# Sheet4.net
KiCad netlist of a schematic drawn in Altium Designer
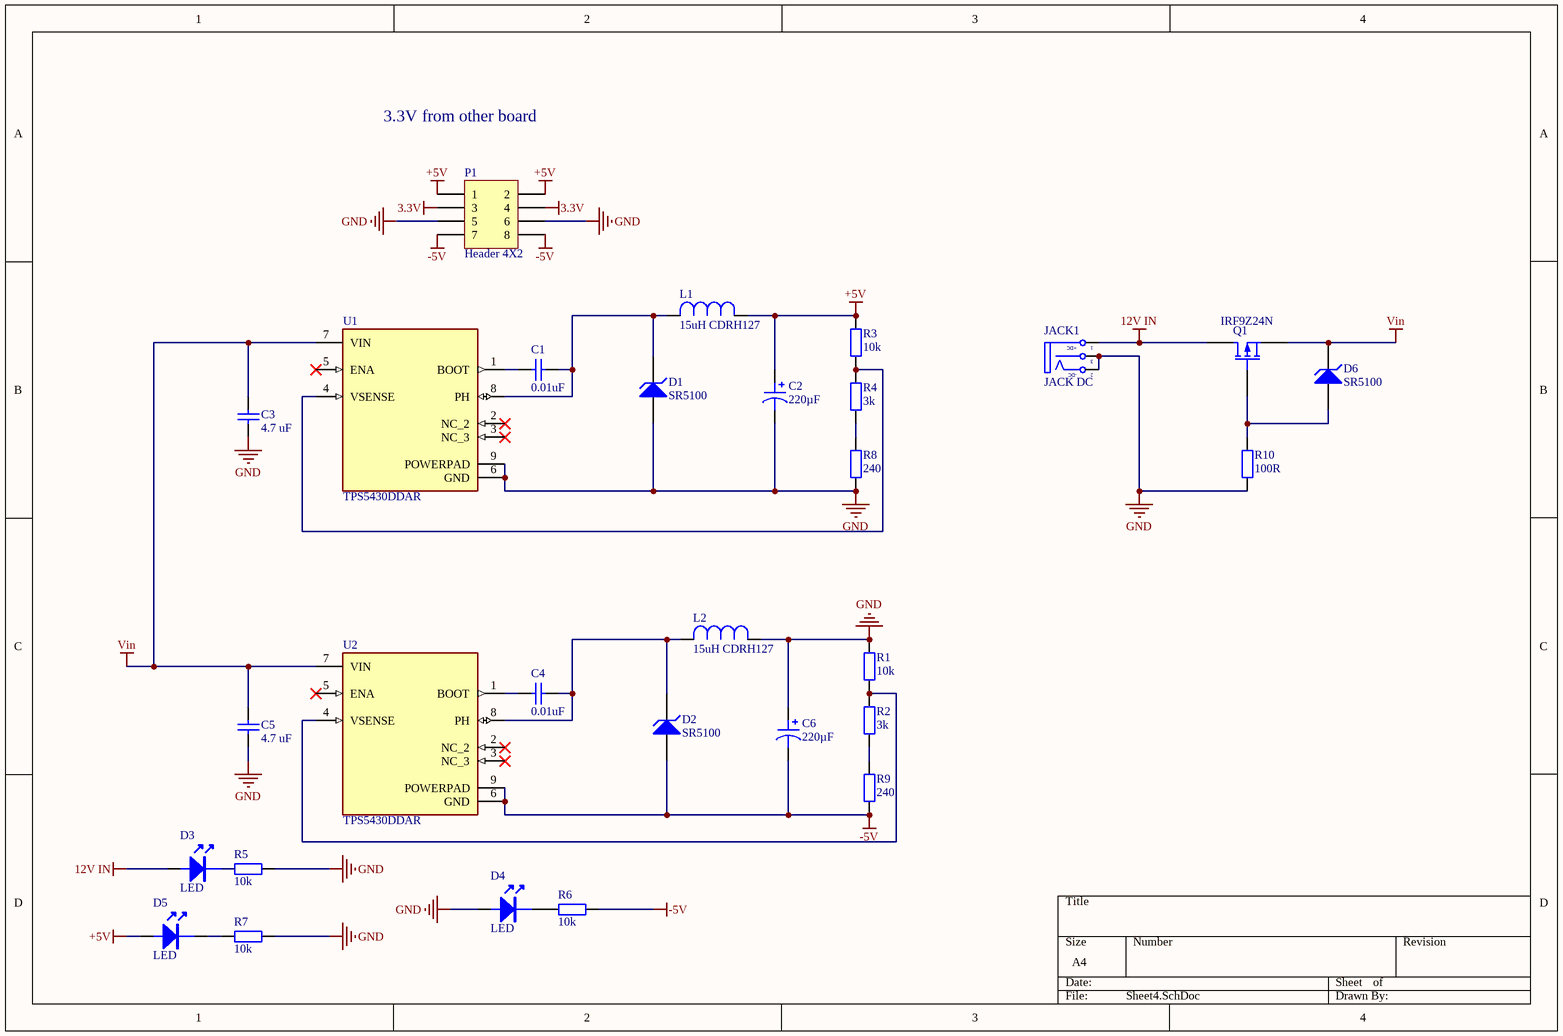
[diagram p0: Sheet4.SchDoc]

(export (version "E")
  (design (tool "Eeschema 10.0.6"))
  (components
    (comp (ref "C1")
      (value "0.01uF")
      (footprint "0805 CAP")
      (fields (field (name "PUBLISHER") "Altium Limited"))
      (libsource (lib "ThinhNguyenLib") (part "CAP CERAMIC"))
    )
    (comp (ref "C2")
      (value "220µF")
      (footprint "CAP POL 2917_7343")
      (description "CAP TANT 330UF 20% 10V 2917")
      (fields (field (name "PART NUMBER") "TPSE337M010R0040") (field (name "MANUFACTURER") "AVX Corporation"))
      (libsource (lib "Celestial Altium Library - altium_library") (part "Polarised Capacitor"))
    )
    (comp (ref "C3")
      (value "4.7 uF")
      (footprint "0805 CAP")
      (fields (field (name "PUBLISHER") "Altium Limited"))
      (libsource (lib "ThinhNguyenLib") (part "CAP CERAMIC"))
    )
    (comp (ref "C4")
      (value "0.01uF")
      (footprint "0805 CAP")
      (fields (field (name "PUBLISHER") "Altium Limited"))
      (libsource (lib "ThinhNguyenLib") (part "CAP CERAMIC"))
    )
    (comp (ref "C5")
      (value "4.7 uF")
      (footprint "0805 CAP")
      (fields (field (name "PUBLISHER") "Altium Limited"))
      (libsource (lib "ThinhNguyenLib") (part "CAP CERAMIC"))
    )
    (comp (ref "C6")
      (value "220µF")
      (footprint "CAP POL 2917_7343")
      (description "CAP TANT 330UF 20% 10V 2917")
      (fields (field (name "PART NUMBER") "TPSE337M010R0040") (field (name "MANUFACTURER") "AVX Corporation"))
      (libsource (lib "Celestial Altium Library - altium_library") (part "Polarised Capacitor"))
    )
    (comp (ref "D1")
      (value "SR5100")
      (footprint "DIODE-0.4")
      (description "Zener Diode")
      (fields (field (name "PUBLISHER") "Altium Limited"))
      (libsource (lib "Miscellaneous Devices") (part "D Zener"))
    )
    (comp (ref "D2")
      (value "SR5100")
      (footprint "DIODE-0.4")
      (description "Zener Diode")
      (fields (field (name "PUBLISHER") "Altium Limited"))
      (libsource (lib "Miscellaneous Devices") (part "D Zener"))
    )
    (comp (ref "D3") (value "LED") (footprint "LED SMD 0805") (libsource (lib "ThinhNguyenLib") (part "LED")))
    (comp (ref "D4") (value "LED") (footprint "LED SMD 0805") (libsource (lib "ThinhNguyenLib") (part "LED")))
    (comp (ref "D5") (value "LED") (footprint "LED SMD 0805") (libsource (lib "ThinhNguyenLib") (part "LED")))
    (comp (ref "D6")
      (value "SR5100")
      (footprint "DIODE-0.4")
      (description "Zener Diode")
      (fields (field (name "PUBLISHER") "Altium Limited"))
      (libsource (lib "Miscellaneous Devices") (part "D Zener"))
    )
    (comp (ref "JACK1")
      (value "JACK DC")
      (footprint "JACK DC")
      (libsource (lib "ThinhNguyenLib") (part "JACK DC"))
    )
    (comp (ref "L1")
      (value "15uH CDRH127")
      (footprint "IND_CDRH127/LDNP-470MC_SUM")
      (description "47ÂµH Shielded Inductor 3.25A 78mOhm Max Nonstandard")
      (fields (field (name "DIGI-KEY_PART_NUMBER") "308-1339-1-ND") (field (name "MF") "Sumida America"))
      (libsource (lib "CDRH127_LDNP-470MC") (part "CDRH127/LDNP-470MC"))
    )
    (comp (ref "L2")
      (value "15uH CDRH127")
      (footprint "IND_CDRH127/LDNP-470MC_SUM")
      (description "47ÂµH Shielded Inductor 3.25A 78mOhm Max Nonstandard")
      (fields (field (name "DIGI-KEY_PART_NUMBER") "308-1339-1-ND") (field (name "MF") "Sumida America"))
      (libsource (lib "CDRH127_LDNP-470MC") (part "CDRH127/LDNP-470MC"))
    )
    (comp (ref "P1")
      (value "Header 4X2")
      (footprint "HDR2X4")
      (fields (field (name "PUBLISHER") "Altium Limited"))
      (libsource (lib "ThinhNguyenLib") (part "Header 4X2"))
    )
    (comp (ref "Q1")
      (value "IRF9Z24N")
      (footprint "TO-220AB")
      (description "P-Channel MOSFET")
      (fields (field (name "PUBLISHER") "Altium Limited"))
      (libsource (lib "Miscellaneous Devices") (part "MOSFET-P"))
    )
    (comp (ref "R1")
      (value "10k")
      (footprint "0805 RESISTOR")
      (libsource (lib "ThinhNguyenLib") (part "RESISTOR"))
    )
    (comp (ref "R2")
      (value "3k")
      (footprint "0805 RESISTOR")
      (libsource (lib "ThinhNguyenLib") (part "RESISTOR"))
    )
    (comp (ref "R3")
      (value "10k")
      (footprint "0805 RESISTOR")
      (libsource (lib "ThinhNguyenLib") (part "RESISTOR"))
    )
    (comp (ref "R4")
      (value "3k")
      (footprint "0805 RESISTOR")
      (libsource (lib "ThinhNguyenLib") (part "RESISTOR"))
    )
    (comp (ref "R5")
      (value "10k")
      (footprint "0805 RESISTOR")
      (libsource (lib "ThinhNguyenLib") (part "RESISTOR"))
    )
    (comp (ref "R6")
      (value "10k")
      (footprint "0805 RESISTOR")
      (libsource (lib "ThinhNguyenLib") (part "RESISTOR"))
    )
    (comp (ref "R7")
      (value "10k")
      (footprint "0805 RESISTOR")
      (libsource (lib "ThinhNguyenLib") (part "RESISTOR"))
    )
    (comp (ref "R8")
      (value "240")
      (footprint "0805 RESISTOR")
      (libsource (lib "ThinhNguyenLib") (part "RESISTOR"))
    )
    (comp (ref "R9")
      (value "240")
      (footprint "0805 RESISTOR")
      (libsource (lib "ThinhNguyenLib") (part "RESISTOR"))
    )
    (comp (ref "R10")
      (value "100R")
      (footprint "0805 RESISTOR")
      (libsource (lib "ThinhNguyenLib") (part "RESISTOR"))
    )
    (comp (ref "U1")
      (value "TPS5430DDAR")
      (footprint "CONV_TPS5430DDAR:CONV_TPS5430DDAR")
      (description "5.5V to 36V Input, 3A, 500kHz Step-Down Converter 8-SO PowerPAD -40 to 125")
      (fields (field (name "DIGI-KEY_PART_NUMBER") "296-26988-1-ND") (field (name "MF") "Texas Instruments"))
      (libsource (lib "TPS5430DDAR") (part "TPS5430DDAR"))
    )
    (comp (ref "U2")
      (value "TPS5430DDAR")
      (footprint "CONV_TPS5430DDAR:CONV_TPS5430DDAR")
      (description "5.5V to 36V Input, 3A, 500kHz Step-Down Converter 8-SO PowerPAD -40 to 125")
      (fields (field (name "DIGI-KEY_PART_NUMBER") "296-26988-1-ND") (field (name "MF") "Texas Instruments"))
      (libsource (lib "TPS5430DDAR") (part "TPS5430DDAR"))
    )
  )
  (nets
    (net (code "1") (name "+5V") (class "Default")
      (node (ref "C2") (pin "1") (pinfunction "1_1") (pintype "passive"))
      (node (ref "D5") (pin "1") (pinfunction "1_1") (pintype "passive"))
      (node (ref "L1") (pin "1") (pinfunction "1_1") (pintype "passive"))
      (node (ref "P1") (pin "1") (pinfunction "1_1") (pintype "passive"))
      (node (ref "P1") (pin "2") (pinfunction "2_2") (pintype "passive"))
      (node (ref "R3") (pin "2") (pinfunction "2_2") (pintype "passive"))
    )
    (net (code "2") (name "-5V") (class "Default")
      (node (ref "C6") (pin "2") (pinfunction "2_2") (pintype "passive"))
      (node (ref "D2") (pin "1") (pinfunction "A_1") (pintype "passive"))
      (node (ref "P1") (pin "7") (pinfunction "7_7") (pintype "passive"))
      (node (ref "P1") (pin "8") (pinfunction "8_8") (pintype "passive"))
      (node (ref "R6") (pin "2") (pinfunction "2_2") (pintype "passive"))
      (node (ref "R9") (pin "1") (pinfunction "1_1") (pintype "passive"))
      (node (ref "U2") (pin "6") (pinfunction "GND_6") (pintype "power_in"))
      (node (ref "U2") (pin "9") (pinfunction "POWERPAD_9") (pintype "power_in"))
    )
    (net (code "3") (name "3.3V") (class "Default")
      (node (ref "P1") (pin "3") (pinfunction "3_3") (pintype "passive"))
      (node (ref "P1") (pin "4") (pinfunction "4_4") (pintype "passive"))
    )
    (net (code "4") (name "12V IN") (class "Default")
      (node (ref "D3") (pin "1") (pinfunction "1_1") (pintype "passive"))
      (node (ref "JACK1") (pin "1") (pinfunction "T_1") (pintype "passive"))
      (node (ref "Q1") (pin "1") (pinfunction "D_1") (pintype "passive"))
    )
    (net (code "5") (name "GND") (class "Default")
      (node (ref "C2") (pin "2") (pinfunction "2_2") (pintype "passive"))
      (node (ref "C3") (pin "1") (pinfunction "1_1") (pintype "passive"))
      (node (ref "C5") (pin "1") (pinfunction "1_1") (pintype "passive"))
      (node (ref "C6") (pin "1") (pinfunction "1_1") (pintype "passive"))
      (node (ref "D1") (pin "1") (pinfunction "A_1") (pintype "passive"))
      (node (ref "D4") (pin "1") (pinfunction "1_1") (pintype "passive"))
      (node (ref "JACK1") (pin "2") (pinfunction "TN_2") (pintype "passive"))
      (node (ref "JACK1") (pin "3") (pinfunction "S_3") (pintype "power_in"))
      (node (ref "L2") (pin "1") (pinfunction "1_1") (pintype "passive"))
      (node (ref "P1") (pin "5") (pinfunction "5_5") (pintype "passive"))
      (node (ref "P1") (pin "6") (pinfunction "6_6") (pintype "passive"))
      (node (ref "R1") (pin "2") (pinfunction "2_2") (pintype "passive"))
      (node (ref "R10") (pin "1") (pinfunction "1_1") (pintype "passive"))
      (node (ref "R5") (pin "2") (pinfunction "2_2") (pintype "passive"))
      (node (ref "R7") (pin "2") (pinfunction "2_2") (pintype "passive"))
      (node (ref "R8") (pin "1") (pinfunction "1_1") (pintype "passive"))
      (node (ref "U1") (pin "6") (pinfunction "GND_6") (pintype "power_in"))
      (node (ref "U1") (pin "9") (pinfunction "POWERPAD_9") (pintype "power_in"))
    )
    (net (code "6") (name "Net-(D1-K)") (class "Default")
      (node (ref "C1") (pin "2") (pinfunction "2_2") (pintype "passive"))
      (node (ref "D1") (pin "2") (pinfunction "K_2") (pintype "passive"))
      (node (ref "L1") (pin "2") (pinfunction "2_2") (pintype "passive"))
      (node (ref "U1") (pin "8") (pinfunction "PH_8") (pintype "bidirectional"))
    )
    (net (code "7") (name "Net-(D2-K)") (class "Default")
      (node (ref "C4") (pin "2") (pinfunction "2_2") (pintype "passive"))
      (node (ref "D2") (pin "2") (pinfunction "K_2") (pintype "passive"))
      (node (ref "L2") (pin "2") (pinfunction "2_2") (pintype "passive"))
      (node (ref "U2") (pin "8") (pinfunction "PH_8") (pintype "bidirectional"))
    )
    (net (code "8") (name "Net-(D3-Pad2)") (class "Default")
      (node (ref "D3") (pin "2") (pinfunction "2_2") (pintype "passive"))
      (node (ref "R5") (pin "1") (pinfunction "1_1") (pintype "passive"))
    )
    (net (code "9") (name "Net-(D4-Pad2)") (class "Default")
      (node (ref "D4") (pin "2") (pinfunction "2_2") (pintype "passive"))
      (node (ref "R6") (pin "1") (pinfunction "1_1") (pintype "passive"))
    )
    (net (code "10") (name "Net-(D5-Pad2)") (class "Default")
      (node (ref "D5") (pin "2") (pinfunction "2_2") (pintype "passive"))
      (node (ref "R7") (pin "1") (pinfunction "1_1") (pintype "passive"))
    )
    (net (code "11") (name "Net-(D6-A)") (class "Default")
      (node (ref "D6") (pin "1") (pinfunction "A_1") (pintype "passive"))
      (node (ref "Q1") (pin "2") (pinfunction "G_2") (pintype "passive"))
      (node (ref "R10") (pin "2") (pinfunction "2_2") (pintype "passive"))
    )
    (net (code "12") (name "Net-(R2-Pad1)") (class "Default")
      (node (ref "R2") (pin "1") (pinfunction "1_1") (pintype "passive"))
      (node (ref "R9") (pin "2") (pinfunction "2_2") (pintype "passive"))
    )
    (net (code "13") (name "Net-(R4-Pad1)") (class "Default")
      (node (ref "R4") (pin "1") (pinfunction "1_1") (pintype "passive"))
      (node (ref "R8") (pin "2") (pinfunction "2_2") (pintype "passive"))
    )
    (net (code "14") (name "Net-(U1-BOOT)") (class "Default")
      (node (ref "C1") (pin "1") (pinfunction "1_1") (pintype "passive"))
      (node (ref "U1") (pin "1") (pinfunction "BOOT_1") (pintype "output"))
    )
    (net (code "15") (name "Net-(U1-VSENSE)") (class "Default")
      (node (ref "R3") (pin "1") (pinfunction "1_1") (pintype "passive"))
      (node (ref "R4") (pin "2") (pinfunction "2_2") (pintype "passive"))
      (node (ref "U1") (pin "4") (pinfunction "VSENSE_4") (pintype "input"))
    )
    (net (code "16") (name "Net-(U2-BOOT)") (class "Default")
      (node (ref "C4") (pin "1") (pinfunction "1_1") (pintype "passive"))
      (node (ref "U2") (pin "1") (pinfunction "BOOT_1") (pintype "output"))
    )
    (net (code "17") (name "Net-(U2-VSENSE)") (class "Default")
      (node (ref "R1") (pin "1") (pinfunction "1_1") (pintype "passive"))
      (node (ref "R2") (pin "2") (pinfunction "2_2") (pintype "passive"))
      (node (ref "U2") (pin "4") (pinfunction "VSENSE_4") (pintype "input"))
    )
    (net (code "18") (name "Vin") (class "Default")
      (node (ref "C3") (pin "2") (pinfunction "2_2") (pintype "passive"))
      (node (ref "C5") (pin "2") (pinfunction "2_2") (pintype "passive"))
      (node (ref "D6") (pin "2") (pinfunction "K_2") (pintype "passive"))
      (node (ref "Q1") (pin "3") (pinfunction "S_3") (pintype "passive"))
      (node (ref "U1") (pin "7") (pinfunction "VIN_7") (pintype "power_in"))
      (node (ref "U2") (pin "7") (pinfunction "VIN_7") (pintype "power_in"))
    )
    (net (code "19") (name "unconnected-(U1-ENA-Pad5)") (class "Default")
      (node (ref "U1") (pin "5") (pinfunction "ENA_5") (pintype "input+no_connect"))
    )
    (net (code "20") (name "unconnected-(U1-NC_2-Pad2)") (class "Default")
      (node (ref "U1") (pin "2") (pinfunction "NC_2_2") (pintype "input+no_connect"))
    )
    (net (code "21") (name "unconnected-(U1-NC_3-Pad3)") (class "Default")
      (node (ref "U1") (pin "3") (pinfunction "NC_3_3") (pintype "input+no_connect"))
    )
    (net (code "22") (name "unconnected-(U2-ENA-Pad5)") (class "Default")
      (node (ref "U2") (pin "5") (pinfunction "ENA_5") (pintype "input+no_connect"))
    )
    (net (code "23") (name "unconnected-(U2-NC_2-Pad2)") (class "Default")
      (node (ref "U2") (pin "2") (pinfunction "NC_2_2") (pintype "input+no_connect"))
    )
    (net (code "24") (name "unconnected-(U2-NC_3-Pad3)") (class "Default")
      (node (ref "U2") (pin "3") (pinfunction "NC_3_3") (pintype "input+no_connect"))
    )
  )
)
